# SensorController.net
KiCad netlist of a schematic drawn in EAGLE
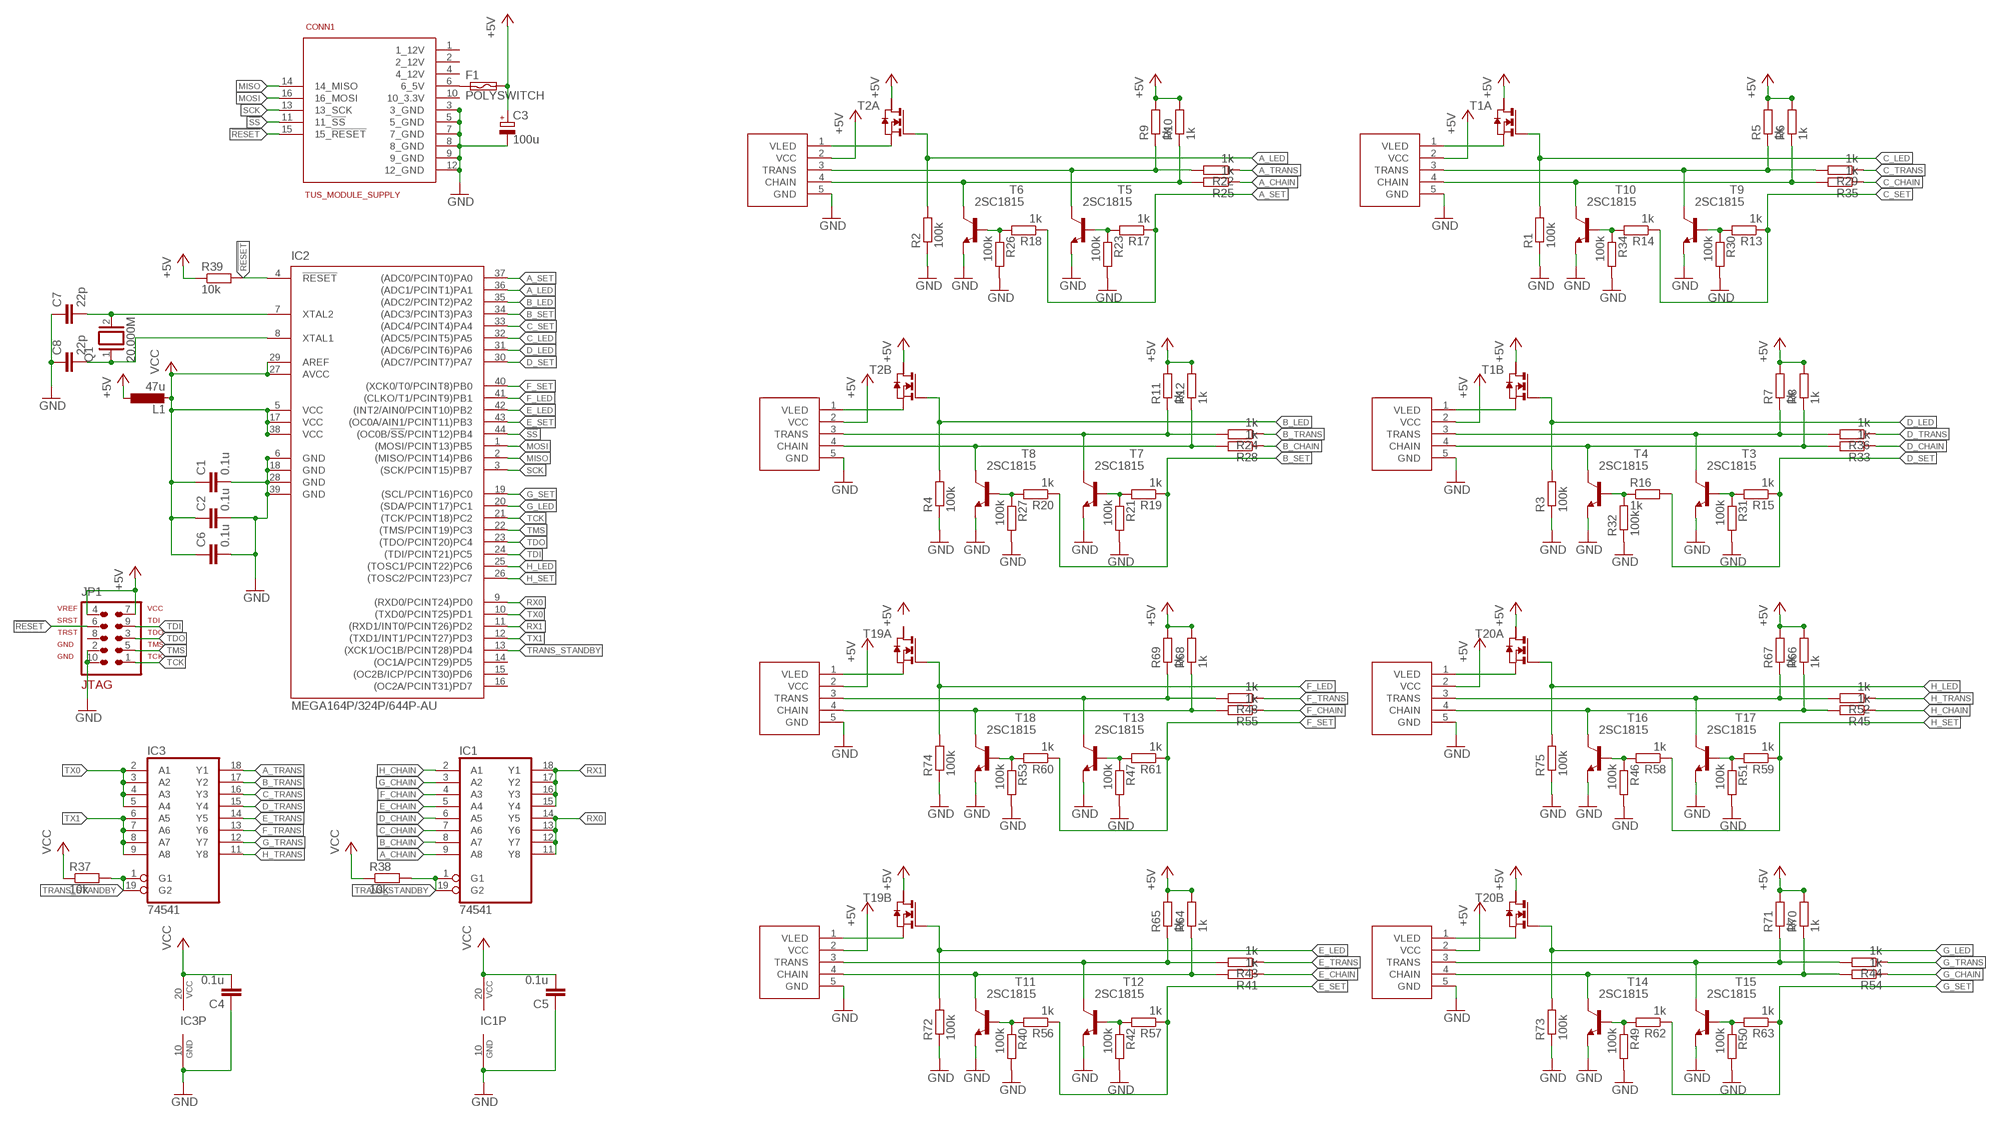
[diagram p0: schematic, sheet 1]

(export (version "E")
  (design (tool "Eeschema 10.0.6"))
  (components
    (comp (ref "A_OUT")
      (value "SERIAL_SENSORXH")
      (footprint "eagle-import:XH-5")
      (libsource (lib "eagle-import") (part "SERIAL_SENSORXH"))
    )
    (comp (ref "B_OUT")
      (value "SERIAL_SENSORXH")
      (footprint "eagle-import:XH-5")
      (libsource (lib "eagle-import") (part "SERIAL_SENSORXH"))
    )
    (comp (ref "C1")
      (value "0.1u")
      (footprint "eagle-import:C1608")
      (libsource (lib "eagle-import") (part "C-EUC1608"))
    )
    (comp (ref "C2")
      (value "0.1u")
      (footprint "eagle-import:C1608")
      (libsource (lib "eagle-import") (part "C-EUC1608"))
    )
    (comp (ref "C3")
      (value "100u")
      (footprint "eagle-import:E2,5-7")
      (libsource (lib "eagle-import") (part "CPOL-EUE2.5-7"))
    )
    (comp (ref "C4")
      (value "0.1u")
      (footprint "eagle-import:C1608")
      (libsource (lib "eagle-import") (part "C-EUC1608"))
    )
    (comp (ref "C5")
      (value "0.1u")
      (footprint "eagle-import:C1608")
      (libsource (lib "eagle-import") (part "C-EUC1608"))
    )
    (comp (ref "C6")
      (value "0.1u")
      (footprint "eagle-import:C1608")
      (libsource (lib "eagle-import") (part "C-EUC1608"))
    )
    (comp (ref "C7")
      (value "22p")
      (footprint "eagle-import:C1608")
      (libsource (lib "eagle-import") (part "C-EUC1608"))
    )
    (comp (ref "C8")
      (value "22p")
      (footprint "eagle-import:C1608")
      (libsource (lib "eagle-import") (part "C-EUC1608"))
    )
    (comp (ref "CONN1")
      (value "TUS_MODULE_SUPPLY")
      (footprint "eagle-import:2X08")
      (libsource (lib "eagle-import") (part "TUS_MODULE_SUPPLY"))
    )
    (comp (ref "C_OUT")
      (value "SERIAL_SENSORXH")
      (footprint "eagle-import:XH-5")
      (libsource (lib "eagle-import") (part "SERIAL_SENSORXH"))
    )
    (comp (ref "D_OUT")
      (value "SERIAL_SENSORXH")
      (footprint "eagle-import:XH-5")
      (libsource (lib "eagle-import") (part "SERIAL_SENSORXH"))
    )
    (comp (ref "E_OUT")
      (value "SERIAL_SENSORXH")
      (footprint "eagle-import:XH-5")
      (libsource (lib "eagle-import") (part "SERIAL_SENSORXH"))
    )
    (comp (ref "F1")
      (value "POLYSWITCH")
      (footprint "eagle-import:0207_2V")
      (libsource (lib "eagle-import") (part "POLYSWITCH"))
    )
    (comp (ref "F_OUT")
      (value "SERIAL_SENSORXH")
      (footprint "eagle-import:XH-5")
      (libsource (lib "eagle-import") (part "SERIAL_SENSORXH"))
    )
    (comp (ref "G_OUT")
      (value "SERIAL_SENSORXH")
      (footprint "eagle-import:XH-5")
      (libsource (lib "eagle-import") (part "SERIAL_SENSORXH"))
    )
    (comp (ref "H_OUT")
      (value "SERIAL_SENSORXH")
      (footprint "eagle-import:XH-5")
      (libsource (lib "eagle-import") (part "SERIAL_SENSORXH"))
    )
    (comp (ref "IC1")
      (value "74541")
      (footprint "eagle-import:SSOP20")
      (libsource (lib "eagle-import") (part "74541"))
    )
    (comp (ref "IC2")
      (value "MEGA164P/324P/644P-AU")
      (footprint "eagle-import:TQFP44")
      (libsource (lib "eagle-import") (part "MEGA164P/324P/644P-AU"))
    )
    (comp (ref "IC3")
      (value "74541")
      (footprint "eagle-import:SSOP20")
      (libsource (lib "eagle-import") (part "74541"))
    )
    (comp (ref "JP1")
      (value "AVR-JTAG-10")
      (footprint "eagle-import:AVR-JTAG-10")
      (libsource (lib "eagle-import") (part "AVR-JTAG-10"))
    )
    (comp (ref "L1")
      (value "47u")
      (footprint "eagle-import:L1812")
      (libsource (lib "eagle-import") (part "L-EUL1812"))
    )
    (comp (ref "Q1")
      (value "20.000M")
      (footprint "eagle-import:QS")
      (libsource (lib "eagle-import") (part "XTAL/S"))
    )
    (comp (ref "R1")
      (value "100k")
      (footprint "eagle-import:R0603")
      (libsource (lib "eagle-import") (part "R-EU_R0603"))
    )
    (comp (ref "R2")
      (value "100k")
      (footprint "eagle-import:R0603")
      (libsource (lib "eagle-import") (part "R-EU_R0603"))
    )
    (comp (ref "R3")
      (value "100k")
      (footprint "eagle-import:R0603")
      (libsource (lib "eagle-import") (part "R-EU_R0603"))
    )
    (comp (ref "R4")
      (value "100k")
      (footprint "eagle-import:R0603")
      (libsource (lib "eagle-import") (part "R-EU_R0603"))
    )
    (comp (ref "R5")
      (value "1k")
      (footprint "eagle-import:R0603")
      (libsource (lib "eagle-import") (part "R-EU_R0603"))
    )
    (comp (ref "R6")
      (value "1k")
      (footprint "eagle-import:R0603")
      (libsource (lib "eagle-import") (part "R-EU_R0603"))
    )
    (comp (ref "R7")
      (value "1k")
      (footprint "eagle-import:R0603")
      (libsource (lib "eagle-import") (part "R-EU_R0603"))
    )
    (comp (ref "R8")
      (value "1k")
      (footprint "eagle-import:R0603")
      (libsource (lib "eagle-import") (part "R-EU_R0603"))
    )
    (comp (ref "R9")
      (value "1k")
      (footprint "eagle-import:R0603")
      (libsource (lib "eagle-import") (part "R-EU_R0603"))
    )
    (comp (ref "R10")
      (value "1k")
      (footprint "eagle-import:R0603")
      (libsource (lib "eagle-import") (part "R-EU_R0603"))
    )
    (comp (ref "R11")
      (value "1k")
      (footprint "eagle-import:R0603")
      (libsource (lib "eagle-import") (part "R-EU_R0603"))
    )
    (comp (ref "R12")
      (value "1k")
      (footprint "eagle-import:R0603")
      (libsource (lib "eagle-import") (part "R-EU_R0603"))
    )
    (comp (ref "R13")
      (value "1k")
      (footprint "eagle-import:R0603")
      (libsource (lib "eagle-import") (part "R-EU_R0603"))
    )
    (comp (ref "R14")
      (value "1k")
      (footprint "eagle-import:R0603")
      (libsource (lib "eagle-import") (part "resistor_R-EU_R0603"))
    )
    (comp (ref "R15")
      (value "1k")
      (footprint "eagle-import:R0603")
      (libsource (lib "eagle-import") (part "R-EU_R0603"))
    )
    (comp (ref "R16")
      (value "1k")
      (footprint "eagle-import:R0603")
      (libsource (lib "eagle-import") (part "R-EU_R0603"))
    )
    (comp (ref "R17")
      (value "1k")
      (footprint "eagle-import:R0603")
      (libsource (lib "eagle-import") (part "R-EU_R0603"))
    )
    (comp (ref "R18")
      (value "1k")
      (footprint "eagle-import:R0603")
      (libsource (lib "eagle-import") (part "R-EU_R0603"))
    )
    (comp (ref "R19")
      (value "1k")
      (footprint "eagle-import:R0603")
      (libsource (lib "eagle-import") (part "R-EU_R0603"))
    )
    (comp (ref "R20")
      (value "1k")
      (footprint "eagle-import:R0603")
      (libsource (lib "eagle-import") (part "R-EU_R0603"))
    )
    (comp (ref "R21")
      (value "100k")
      (footprint "eagle-import:R0603")
      (libsource (lib "eagle-import") (part "R-EU_R0603"))
    )
    (comp (ref "R22")
      (value "1k")
      (footprint "eagle-import:R0603")
      (libsource (lib "eagle-import") (part "R-EU_R0603"))
    )
    (comp (ref "R23")
      (value "100k")
      (footprint "eagle-import:R0603")
      (libsource (lib "eagle-import") (part "R-EU_R0603"))
    )
    (comp (ref "R24")
      (value "1k")
      (footprint "eagle-import:R0603")
      (libsource (lib "eagle-import") (part "R-EU_R0603"))
    )
    (comp (ref "R25")
      (value "1k")
      (footprint "eagle-import:R0603")
      (libsource (lib "eagle-import") (part "R-EU_R0603"))
    )
    (comp (ref "R26")
      (value "100k")
      (footprint "eagle-import:R0603")
      (libsource (lib "eagle-import") (part "R-EU_R0603"))
    )
    (comp (ref "R27")
      (value "100k")
      (footprint "eagle-import:R0603")
      (libsource (lib "eagle-import") (part "R-EU_R0603"))
    )
    (comp (ref "R28")
      (value "1k")
      (footprint "eagle-import:R0603")
      (libsource (lib "eagle-import") (part "R-EU_R0603"))
    )
    (comp (ref "R29")
      (value "1k")
      (footprint "eagle-import:R0603")
      (libsource (lib "eagle-import") (part "R-EU_R0603"))
    )
    (comp (ref "R30")
      (value "100k")
      (footprint "eagle-import:R0603")
      (libsource (lib "eagle-import") (part "R-EU_R0603"))
    )
    (comp (ref "R31")
      (value "100k")
      (footprint "eagle-import:R0603")
      (libsource (lib "eagle-import") (part "R-EU_R0603"))
    )
    (comp (ref "R32")
      (value "100k")
      (footprint "eagle-import:R0603")
      (libsource (lib "eagle-import") (part "R-EU_R0603"))
    )
    (comp (ref "R33")
      (value "1k")
      (footprint "eagle-import:R0603")
      (libsource (lib "eagle-import") (part "R-EU_R0603"))
    )
    (comp (ref "R34")
      (value "100k")
      (footprint "eagle-import:R0603")
      (libsource (lib "eagle-import") (part "resistor_R-EU_R0603"))
    )
    (comp (ref "R35")
      (value "1k")
      (footprint "eagle-import:R0603")
      (libsource (lib "eagle-import") (part "R-EU_R0603"))
    )
    (comp (ref "R36")
      (value "1k")
      (footprint "eagle-import:R0603")
      (libsource (lib "eagle-import") (part "R-EU_R0603"))
    )
    (comp (ref "R37")
      (value "10k")
      (footprint "eagle-import:R0603")
      (libsource (lib "eagle-import") (part "R-EU_R0603"))
    )
    (comp (ref "R38")
      (value "10k")
      (footprint "eagle-import:R0603")
      (libsource (lib "eagle-import") (part "R-EU_R0603"))
    )
    (comp (ref "R39")
      (value "10k")
      (footprint "eagle-import:R0603")
      (libsource (lib "eagle-import") (part "R-EU_R0603"))
    )
    (comp (ref "R40")
      (value "100k")
      (footprint "eagle-import:R0603")
      (libsource (lib "eagle-import") (part "R-EU_R0603"))
    )
    (comp (ref "R41")
      (value "1k")
      (footprint "eagle-import:R0603")
      (libsource (lib "eagle-import") (part "R-EU_R0603"))
    )
    (comp (ref "R42")
      (value "100k")
      (footprint "eagle-import:R0603")
      (libsource (lib "eagle-import") (part "R-EU_R0603"))
    )
    (comp (ref "R43")
      (value "1k")
      (footprint "eagle-import:R0603")
      (libsource (lib "eagle-import") (part "R-EU_R0603"))
    )
    (comp (ref "R44")
      (value "1k")
      (footprint "eagle-import:R0603")
      (libsource (lib "eagle-import") (part "R-EU_R0603"))
    )
    (comp (ref "R45")
      (value "1k")
      (footprint "eagle-import:R0603")
      (libsource (lib "eagle-import") (part "R-EU_R0603"))
    )
    (comp (ref "R46")
      (value "100k")
      (footprint "eagle-import:R0603")
      (libsource (lib "eagle-import") (part "R-EU_R0603"))
    )
    (comp (ref "R47")
      (value "100k")
      (footprint "eagle-import:R0603")
      (libsource (lib "eagle-import") (part "R-EU_R0603"))
    )
    (comp (ref "R48")
      (value "1k")
      (footprint "eagle-import:R0603")
      (libsource (lib "eagle-import") (part "R-EU_R0603"))
    )
    (comp (ref "R49")
      (value "100k")
      (footprint "eagle-import:R0603")
      (libsource (lib "eagle-import") (part "R-EU_R0603"))
    )
    (comp (ref "R50")
      (value "100k")
      (footprint "eagle-import:R0603")
      (libsource (lib "eagle-import") (part "R-EU_R0603"))
    )
    (comp (ref "R51")
      (value "100k")
      (footprint "eagle-import:R0603")
      (libsource (lib "eagle-import") (part "R-EU_R0603"))
    )
    (comp (ref "R52")
      (value "1k")
      (footprint "eagle-import:R0603")
      (libsource (lib "eagle-import") (part "R-EU_R0603"))
    )
    (comp (ref "R53")
      (value "100k")
      (footprint "eagle-import:R0603")
      (libsource (lib "eagle-import") (part "R-EU_R0603"))
    )
    (comp (ref "R54")
      (value "1k")
      (footprint "eagle-import:R0603")
      (libsource (lib "eagle-import") (part "R-EU_R0603"))
    )
    (comp (ref "R55")
      (value "1k")
      (footprint "eagle-import:R0603")
      (libsource (lib "eagle-import") (part "R-EU_R0603"))
    )
    (comp (ref "R56")
      (value "1k")
      (footprint "eagle-import:R0603")
      (libsource (lib "eagle-import") (part "R-EU_R0603"))
    )
    (comp (ref "R57")
      (value "1k")
      (footprint "eagle-import:R0603")
      (libsource (lib "eagle-import") (part "R-EU_R0603"))
    )
    (comp (ref "R58")
      (value "1k")
      (footprint "eagle-import:R0603")
      (libsource (lib "eagle-import") (part "R-EU_R0603"))
    )
    (comp (ref "R59")
      (value "1k")
      (footprint "eagle-import:R0603")
      (libsource (lib "eagle-import") (part "R-EU_R0603"))
    )
    (comp (ref "R60")
      (value "1k")
      (footprint "eagle-import:R0603")
      (libsource (lib "eagle-import") (part "R-EU_R0603"))
    )
    (comp (ref "R61")
      (value "1k")
      (footprint "eagle-import:R0603")
      (libsource (lib "eagle-import") (part "R-EU_R0603"))
    )
    (comp (ref "R62")
      (value "1k")
      (footprint "eagle-import:R0603")
      (libsource (lib "eagle-import") (part "R-EU_R0603"))
    )
    (comp (ref "R63")
      (value "1k")
      (footprint "eagle-import:R0603")
      (libsource (lib "eagle-import") (part "R-EU_R0603"))
    )
    (comp (ref "R64")
      (value "1k")
      (footprint "eagle-import:R0603")
      (libsource (lib "eagle-import") (part "R-EU_R0603"))
    )
    (comp (ref "R65")
      (value "1k")
      (footprint "eagle-import:R0603")
      (libsource (lib "eagle-import") (part "R-EU_R0603"))
    )
    (comp (ref "R66")
      (value "1k")
      (footprint "eagle-import:R0603")
      (libsource (lib "eagle-import") (part "R-EU_R0603"))
    )
    (comp (ref "R67")
      (value "1k")
      (footprint "eagle-import:R0603")
      (libsource (lib "eagle-import") (part "R-EU_R0603"))
    )
    (comp (ref "R68")
      (value "1k")
      (footprint "eagle-import:R0603")
      (libsource (lib "eagle-import") (part "R-EU_R0603"))
    )
    (comp (ref "R69")
      (value "1k")
      (footprint "eagle-import:R0603")
      (libsource (lib "eagle-import") (part "R-EU_R0603"))
    )
    (comp (ref "R70")
      (value "1k")
      (footprint "eagle-import:R0603")
      (libsource (lib "eagle-import") (part "R-EU_R0603"))
    )
    (comp (ref "R71")
      (value "1k")
      (footprint "eagle-import:R0603")
      (libsource (lib "eagle-import") (part "R-EU_R0603"))
    )
    (comp (ref "R72")
      (value "100k")
      (footprint "eagle-import:R0603")
      (libsource (lib "eagle-import") (part "R-EU_R0603"))
    )
    (comp (ref "R73")
      (value "100k")
      (footprint "eagle-import:R0603")
      (libsource (lib "eagle-import") (part "R-EU_R0603"))
    )
    (comp (ref "R74")
      (value "100k")
      (footprint "eagle-import:R0603")
      (libsource (lib "eagle-import") (part "R-EU_R0603"))
    )
    (comp (ref "R75")
      (value "100k")
      (footprint "eagle-import:R0603")
      (libsource (lib "eagle-import") (part "R-EU_R0603"))
    )
    (comp (ref "T1")
      (value "NMOS2SO8")
      (footprint "eagle-import:SO8")
      (fields (field (name "OC_FARNELL") "unknown") (field (name "OC_NEWARK") "unknown"))
      (libsource (lib "eagle-import") (part "NMOS2SO8"))
    )
    (comp (ref "T2")
      (value "NMOS2SO8")
      (footprint "eagle-import:SO8")
      (libsource (lib "eagle-import") (part "NMOS2SO8"))
    )
    (comp (ref "T3")
      (value "2SC1815")
      (footprint "eagle-import:TO92-ECB")
      (libsource (lib "eagle-import") (part "2SC1815"))
    )
    (comp (ref "T4")
      (value "2SC1815")
      (footprint "eagle-import:TO92-ECB")
      (libsource (lib "eagle-import") (part "2SC1815"))
    )
    (comp (ref "T5")
      (value "2SC1815")
      (footprint "eagle-import:TO92-ECB")
      (libsource (lib "eagle-import") (part "2SC1815"))
    )
    (comp (ref "T6")
      (value "2SC1815")
      (footprint "eagle-import:TO92-ECB")
      (libsource (lib "eagle-import") (part "2SC1815"))
    )
    (comp (ref "T7")
      (value "2SC1815")
      (footprint "eagle-import:TO92-ECB")
      (libsource (lib "eagle-import") (part "2SC1815"))
    )
    (comp (ref "T8")
      (value "2SC1815")
      (footprint "eagle-import:TO92-ECB")
      (libsource (lib "eagle-import") (part "2SC1815"))
    )
    (comp (ref "T9")
      (value "2SC1815")
      (footprint "eagle-import:TO92-ECB")
      (libsource (lib "eagle-import") (part "2SC1815"))
    )
    (comp (ref "T10")
      (value "2SC1815")
      (footprint "eagle-import:TO92-ECB")
      (libsource (lib "eagle-import") (part "2SC1815"))
    )
    (comp (ref "T11")
      (value "2SC1815")
      (footprint "eagle-import:TO92-ECB")
      (libsource (lib "eagle-import") (part "2SC1815"))
    )
    (comp (ref "T12")
      (value "2SC1815")
      (footprint "eagle-import:TO92-ECB")
      (libsource (lib "eagle-import") (part "2SC1815"))
    )
    (comp (ref "T13")
      (value "2SC1815")
      (footprint "eagle-import:TO92-ECB")
      (libsource (lib "eagle-import") (part "2SC1815"))
    )
    (comp (ref "T14")
      (value "2SC1815")
      (footprint "eagle-import:TO92-ECB")
      (libsource (lib "eagle-import") (part "2SC1815"))
    )
    (comp (ref "T15")
      (value "2SC1815")
      (footprint "eagle-import:TO92-ECB")
      (libsource (lib "eagle-import") (part "2SC1815"))
    )
    (comp (ref "T16")
      (value "2SC1815")
      (footprint "eagle-import:TO92-ECB")
      (libsource (lib "eagle-import") (part "2SC1815"))
    )
    (comp (ref "T17")
      (value "2SC1815")
      (footprint "eagle-import:TO92-ECB")
      (libsource (lib "eagle-import") (part "2SC1815"))
    )
    (comp (ref "T18")
      (value "2SC1815")
      (footprint "eagle-import:TO92-ECB")
      (libsource (lib "eagle-import") (part "2SC1815"))
    )
    (comp (ref "T19")
      (value "NMOS2SO8")
      (footprint "eagle-import:SO8")
      (fields (field (name "OC_FARNELL") "unknown") (field (name "OC_NEWARK") "unknown"))
      (libsource (lib "eagle-import") (part "NMOS2SO8"))
    )
    (comp (ref "T20")
      (value "NMOS2SO8")
      (footprint "eagle-import:SO8")
      (fields (field (name "OC_FARNELL") "unknown") (field (name "OC_NEWARK") "unknown"))
      (libsource (lib "eagle-import") (part "NMOS2SO8"))
    )
  )
  (nets
    (net (code "1") (name "+5V") (class "Default")
      (node (ref "A_OUT") (pin "2") (pinfunction "VCC_2") (pintype "bidirectional"))
      (node (ref "B_OUT") (pin "2") (pinfunction "VCC_2") (pintype "bidirectional"))
      (node (ref "C3") (pin "+") (pinfunction "+_+") (pintype "passive"))
      (node (ref "C_OUT") (pin "2") (pinfunction "VCC_2") (pintype "bidirectional"))
      (node (ref "D_OUT") (pin "2") (pinfunction "VCC_2") (pintype "bidirectional"))
      (node (ref "E_OUT") (pin "2") (pinfunction "VCC_2") (pintype "bidirectional"))
      (node (ref "F1") (pin "2") (pinfunction "2_2") (pintype "passive"))
      (node (ref "F_OUT") (pin "2") (pinfunction "VCC_2") (pintype "bidirectional"))
      (node (ref "G_OUT") (pin "2") (pinfunction "VCC_2") (pintype "bidirectional"))
      (node (ref "H_OUT") (pin "2") (pinfunction "VCC_2") (pintype "bidirectional"))
      (node (ref "JP1") (pin "4") (pinfunction "4_4") (pintype "passive"))
      (node (ref "JP1") (pin "7") (pinfunction "7_7") (pintype "passive"))
      (node (ref "L1") (pin "1") (pinfunction "1_1") (pintype "passive"))
      (node (ref "R10") (pin "2") (pinfunction "2_2") (pintype "passive"))
      (node (ref "R11") (pin "2") (pinfunction "2_2") (pintype "passive"))
      (node (ref "R12") (pin "2") (pinfunction "2_2") (pintype "passive"))
      (node (ref "R39") (pin "1") (pinfunction "1_1") (pintype "passive"))
      (node (ref "R5") (pin "2") (pinfunction "2_2") (pintype "passive"))
      (node (ref "R6") (pin "2") (pinfunction "2_2") (pintype "passive"))
      (node (ref "R64") (pin "2") (pinfunction "2_2") (pintype "passive"))
      (node (ref "R65") (pin "2") (pinfunction "2_2") (pintype "passive"))
      (node (ref "R66") (pin "2") (pinfunction "2_2") (pintype "passive"))
      (node (ref "R67") (pin "2") (pinfunction "2_2") (pintype "passive"))
      (node (ref "R68") (pin "2") (pinfunction "2_2") (pintype "passive"))
      (node (ref "R69") (pin "2") (pinfunction "2_2") (pintype "passive"))
      (node (ref "R7") (pin "2") (pinfunction "2_2") (pintype "passive"))
      (node (ref "R70") (pin "2") (pinfunction "2_2") (pintype "passive"))
      (node (ref "R71") (pin "2") (pinfunction "2_2") (pintype "passive"))
      (node (ref "R8") (pin "2") (pinfunction "2_2") (pintype "passive"))
      (node (ref "R9") (pin "2") (pinfunction "2_2") (pintype "passive"))
      (node (ref "T1") (pin "6") (pinfunction "D_6") (pintype "passive"))
      (node (ref "T1") (pin "8") (pinfunction "D_8") (pintype "passive"))
      (node (ref "T19") (pin "6") (pinfunction "D_6") (pintype "passive"))
      (node (ref "T2") (pin "6") (pinfunction "D_6") (pintype "passive"))
      (node (ref "T2") (pin "8") (pinfunction "D_8") (pintype "passive"))
      (node (ref "T20") (pin "6") (pinfunction "D_6") (pintype "passive"))
      (node (ref "T20") (pin "8") (pinfunction "D_8") (pintype "passive"))
    )
    (net (code "2") (name "/~{RESET}") (class "Default")
      (node (ref "CONN1") (pin "15") (pinfunction "15_~{RESET}_15") (pintype "bidirectional"))
      (node (ref "IC2") (pin "4") (pinfunction "~{RESET}_4") (pintype "input"))
      (node (ref "JP1") (pin "6") (pinfunction "6_6") (pintype "passive"))
      (node (ref "R39") (pin "2") (pinfunction "2_2") (pintype "passive"))
    )
    (net (code "3") (name "/~{SS}") (class "Default")
      (node (ref "CONN1") (pin "11") (pinfunction "11_~{SS}_11") (pintype "bidirectional"))
      (node (ref "IC2") (pin "44") (pinfunction "(OC0B/~{SS}/PCINT12)PB4_44") (pintype "bidirectional"))
    )
    (net (code "4") (name "A_CHAIN") (class "Default")
      (node (ref "IC1") (pin "9") (pinfunction "A8_9") (pintype "input"))
      (node (ref "R25") (pin "1") (pinfunction "1_1") (pintype "passive"))
    )
    (net (code "5") (name "A_LED") (class "Default")
      (node (ref "IC2") (pin "36") (pinfunction "(ADC1/PCINT1)PA1_36") (pintype "bidirectional"))
      (node (ref "R2") (pin "2") (pinfunction "2_2") (pintype "passive"))
      (node (ref "T2") (pin "2") (pinfunction "G_2") (pintype "passive"))
    )
    (net (code "6") (name "A_SET") (class "Default")
      (node (ref "IC2") (pin "37") (pinfunction "(ADC0/PCINT0)PA0_37") (pintype "bidirectional"))
      (node (ref "R17") (pin "1") (pinfunction "1_1") (pintype "passive"))
      (node (ref "R18") (pin "1") (pinfunction "1_1") (pintype "passive"))
    )
    (net (code "7") (name "A_TRANS") (class "Default")
      (node (ref "IC3") (pin "18") (pinfunction "Y1_18") (pintype "tri_state"))
      (node (ref "R22") (pin "1") (pinfunction "1_1") (pintype "passive"))
    )
    (net (code "8") (name "B_CHAIN") (class "Default")
      (node (ref "IC1") (pin "8") (pinfunction "A7_8") (pintype "input"))
      (node (ref "R28") (pin "1") (pinfunction "1_1") (pintype "passive"))
    )
    (net (code "9") (name "B_LED") (class "Default")
      (node (ref "IC2") (pin "35") (pinfunction "(ADC2/PCINT2)PA2_35") (pintype "bidirectional"))
      (node (ref "R4") (pin "2") (pinfunction "2_2") (pintype "passive"))
      (node (ref "T2") (pin "4") (pinfunction "G_4") (pintype "passive"))
    )
    (net (code "10") (name "B_SET") (class "Default")
      (node (ref "IC2") (pin "34") (pinfunction "(ADC3/PCINT3)PA3_34") (pintype "bidirectional"))
      (node (ref "R19") (pin "1") (pinfunction "1_1") (pintype "passive"))
      (node (ref "R20") (pin "1") (pinfunction "1_1") (pintype "passive"))
    )
    (net (code "11") (name "B_TRANS") (class "Default")
      (node (ref "IC3") (pin "17") (pinfunction "Y2_17") (pintype "tri_state"))
      (node (ref "R24") (pin "1") (pinfunction "1_1") (pintype "passive"))
    )
    (net (code "12") (name "C_CHAIN") (class "Default")
      (node (ref "IC1") (pin "7") (pinfunction "A6_7") (pintype "input"))
      (node (ref "R35") (pin "1") (pinfunction "1_1") (pintype "passive"))
    )
    (net (code "13") (name "C_LED") (class "Default")
      (node (ref "IC2") (pin "32") (pinfunction "(ADC5/PCINT5)PA5_32") (pintype "bidirectional"))
      (node (ref "R1") (pin "2") (pinfunction "2_2") (pintype "passive"))
      (node (ref "T1") (pin "2") (pinfunction "G_2") (pintype "passive"))
    )
    (net (code "14") (name "C_SET") (class "Default")
      (node (ref "IC2") (pin "33") (pinfunction "(ADC4/PCINT4)PA4_33") (pintype "bidirectional"))
      (node (ref "R13") (pin "1") (pinfunction "1_1") (pintype "passive"))
      (node (ref "R14") (pin "1") (pinfunction "1_1") (pintype "passive"))
    )
    (net (code "15") (name "C_TRANS") (class "Default")
      (node (ref "IC3") (pin "16") (pinfunction "Y3_16") (pintype "tri_state"))
      (node (ref "R29") (pin "1") (pinfunction "1_1") (pintype "passive"))
    )
    (net (code "16") (name "D_CHAIN") (class "Default")
      (node (ref "IC1") (pin "6") (pinfunction "A5_6") (pintype "input"))
      (node (ref "R33") (pin "1") (pinfunction "1_1") (pintype "passive"))
    )
    (net (code "17") (name "D_LED") (class "Default")
      (node (ref "IC2") (pin "31") (pinfunction "(ADC6/PCINT6)PA6_31") (pintype "bidirectional"))
      (node (ref "R3") (pin "2") (pinfunction "2_2") (pintype "passive"))
      (node (ref "T1") (pin "4") (pinfunction "G_4") (pintype "passive"))
    )
    (net (code "18") (name "D_SET") (class "Default")
      (node (ref "IC2") (pin "30") (pinfunction "(ADC7/PCINT7)PA7_30") (pintype "bidirectional"))
      (node (ref "R15") (pin "1") (pinfunction "1_1") (pintype "passive"))
      (node (ref "R16") (pin "2") (pinfunction "2_2") (pintype "passive"))
    )
    (net (code "19") (name "D_TRANS") (class "Default")
      (node (ref "IC3") (pin "15") (pinfunction "Y4_15") (pintype "tri_state"))
      (node (ref "R36") (pin "1") (pinfunction "1_1") (pintype "passive"))
    )
    (net (code "20") (name "E_CHAIN") (class "Default")
      (node (ref "IC1") (pin "5") (pinfunction "A4_5") (pintype "input"))
      (node (ref "R41") (pin "1") (pinfunction "1_1") (pintype "passive"))
    )
    (net (code "21") (name "E_LED") (class "Default")
      (node (ref "IC2") (pin "42") (pinfunction "(INT2/AIN0/PCINT10)PB2_42") (pintype "bidirectional"))
      (node (ref "R72") (pin "2") (pinfunction "2_2") (pintype "passive"))
      (node (ref "T19") (pin "4") (pinfunction "G_4") (pintype "passive"))
    )
    (net (code "22") (name "E_SET") (class "Default")
      (node (ref "IC2") (pin "43") (pinfunction "(OC0A/AIN1/PCINT11)PB3_43") (pintype "bidirectional"))
      (node (ref "R56") (pin "1") (pinfunction "1_1") (pintype "passive"))
      (node (ref "R57") (pin "1") (pinfunction "1_1") (pintype "passive"))
    )
    (net (code "23") (name "E_TRANS") (class "Default")
      (node (ref "IC3") (pin "14") (pinfunction "Y5_14") (pintype "tri_state"))
      (node (ref "R43") (pin "1") (pinfunction "1_1") (pintype "passive"))
    )
    (net (code "24") (name "F_CHAIN") (class "Default")
      (node (ref "IC1") (pin "4") (pinfunction "A3_4") (pintype "input"))
      (node (ref "R55") (pin "1") (pinfunction "1_1") (pintype "passive"))
    )
    (net (code "25") (name "F_LED") (class "Default")
      (node (ref "IC2") (pin "41") (pinfunction "(CLKO/T1/PCINT9)PB1_41") (pintype "bidirectional"))
      (node (ref "R74") (pin "2") (pinfunction "2_2") (pintype "passive"))
      (node (ref "T19") (pin "2") (pinfunction "G_2") (pintype "passive"))
    )
    (net (code "26") (name "F_SET") (class "Default")
      (node (ref "IC2") (pin "40") (pinfunction "(XCK0/T0/PCINT8)PB0_40") (pintype "bidirectional"))
      (node (ref "R60") (pin "1") (pinfunction "1_1") (pintype "passive"))
      (node (ref "R61") (pin "1") (pinfunction "1_1") (pintype "passive"))
    )
    (net (code "27") (name "F_TRANS") (class "Default")
      (node (ref "IC3") (pin "13") (pinfunction "Y6_13") (pintype "tri_state"))
      (node (ref "R48") (pin "1") (pinfunction "1_1") (pintype "passive"))
    )
    (net (code "28") (name "GND") (class "Default")
      (node (ref "A_OUT") (pin "5") (pinfunction "GND_5") (pintype "bidirectional"))
      (node (ref "B_OUT") (pin "5") (pinfunction "GND_5") (pintype "bidirectional"))
      (node (ref "C1") (pin "2") (pinfunction "2_2") (pintype "passive"))
      (node (ref "C2") (pin "2") (pinfunction "2_2") (pintype "passive"))
      (node (ref "C3") (pin "-") (pinfunction "-_-") (pintype "passive"))
      (node (ref "C4") (pin "1") (pinfunction "1_1") (pintype "passive"))
      (node (ref "C5") (pin "1") (pinfunction "1_1") (pintype "passive"))
      (node (ref "C6") (pin "2") (pinfunction "2_2") (pintype "passive"))
      (node (ref "C7") (pin "1") (pinfunction "1_1") (pintype "passive"))
      (node (ref "C8") (pin "1") (pinfunction "1_1") (pintype "passive"))
      (node (ref "CONN1") (pin "12") (pinfunction "12_GND_12") (pintype "bidirectional"))
      (node (ref "CONN1") (pin "3") (pinfunction "3_GND_3") (pintype "bidirectional"))
      (node (ref "CONN1") (pin "5") (pinfunction "5_GND_5") (pintype "bidirectional"))
      (node (ref "CONN1") (pin "7") (pinfunction "7_GND_7") (pintype "bidirectional"))
      (node (ref "CONN1") (pin "8") (pinfunction "8_GND_8") (pintype "bidirectional"))
      (node (ref "CONN1") (pin "9") (pinfunction "9_GND_9") (pintype "bidirectional"))
      (node (ref "C_OUT") (pin "5") (pinfunction "GND_5") (pintype "bidirectional"))
      (node (ref "D_OUT") (pin "5") (pinfunction "GND_5") (pintype "bidirectional"))
      (node (ref "E_OUT") (pin "5") (pinfunction "GND_5") (pintype "bidirectional"))
      (node (ref "F_OUT") (pin "5") (pinfunction "GND_5") (pintype "bidirectional"))
      (node (ref "G_OUT") (pin "5") (pinfunction "GND_5") (pintype "bidirectional"))
      (node (ref "H_OUT") (pin "5") (pinfunction "GND_5") (pintype "bidirectional"))
      (node (ref "IC1") (pin "10") (pinfunction "GND_10") (pintype "power_in"))
      (node (ref "IC2") (pin "18") (pinfunction "GND_18") (pintype "power_in"))
      (node (ref "IC2") (pin "28") (pinfunction "GND_28") (pintype "power_in"))
      (node (ref "IC2") (pin "39") (pinfunction "GND_39") (pintype "power_in"))
      (node (ref "IC2") (pin "6") (pinfunction "GND_6") (pintype "power_in"))
      (node (ref "IC3") (pin "10") (pinfunction "GND_10") (pintype "power_in"))
      (node (ref "JP1") (pin "10") (pinfunction "10_10") (pintype "passive"))
      (node (ref "JP1") (pin "2") (pinfunction "2_2") (pintype "passive"))
      (node (ref "R1") (pin "1") (pinfunction "1_1") (pintype "passive"))
      (node (ref "R2") (pin "1") (pinfunction "1_1") (pintype "passive"))
      (node (ref "R21") (pin "2") (pinfunction "2_2") (pintype "passive"))
      (node (ref "R23") (pin "2") (pinfunction "2_2") (pintype "passive"))
      (node (ref "R26") (pin "2") (pinfunction "2_2") (pintype "passive"))
      (node (ref "R27") (pin "2") (pinfunction "2_2") (pintype "passive"))
      (node (ref "R3") (pin "1") (pinfunction "1_1") (pintype "passive"))
      (node (ref "R30") (pin "2") (pinfunction "2_2") (pintype "passive"))
      (node (ref "R31") (pin "2") (pinfunction "2_2") (pintype "passive"))
      (node (ref "R32") (pin "1") (pinfunction "1_1") (pintype "passive"))
      (node (ref "R34") (pin "2") (pinfunction "2_2") (pintype "passive"))
      (node (ref "R4") (pin "1") (pinfunction "1_1") (pintype "passive"))
      (node (ref "R40") (pin "2") (pinfunction "2_2") (pintype "passive"))
      (node (ref "R42") (pin "2") (pinfunction "2_2") (pintype "passive"))
      (node (ref "R46") (pin "2") (pinfunction "2_2") (pintype "passive"))
      (node (ref "R47") (pin "2") (pinfunction "2_2") (pintype "passive"))
      (node (ref "R49") (pin "2") (pinfunction "2_2") (pintype "passive"))
      (node (ref "R50") (pin "2") (pinfunction "2_2") (pintype "passive"))
      (node (ref "R51") (pin "2") (pinfunction "2_2") (pintype "passive"))
      (node (ref "R53") (pin "2") (pinfunction "2_2") (pintype "passive"))
      (node (ref "R72") (pin "1") (pinfunction "1_1") (pintype "passive"))
      (node (ref "R73") (pin "1") (pinfunction "1_1") (pintype "passive"))
      (node (ref "R74") (pin "1") (pinfunction "1_1") (pintype "passive"))
      (node (ref "R75") (pin "1") (pinfunction "1_1") (pintype "passive"))
      (node (ref "T10") (pin "E") (pinfunction "E_E") (pintype "passive"))
      (node (ref "T11") (pin "E") (pinfunction "E_E") (pintype "passive"))
      (node (ref "T12") (pin "E") (pinfunction "E_E") (pintype "passive"))
      (node (ref "T13") (pin "E") (pinfunction "E_E") (pintype "passive"))
      (node (ref "T14") (pin "E") (pinfunction "E_E") (pintype "passive"))
      (node (ref "T15") (pin "E") (pinfunction "E_E") (pintype "passive"))
      (node (ref "T16") (pin "E") (pinfunction "E_E") (pintype "passive"))
      (node (ref "T17") (pin "E") (pinfunction "E_E") (pintype "passive"))
      (node (ref "T18") (pin "E") (pinfunction "E_E") (pintype "passive"))
      (node (ref "T3") (pin "E") (pinfunction "E_E") (pintype "passive"))
      (node (ref "T4") (pin "E") (pinfunction "E_E") (pintype "passive"))
      (node (ref "T5") (pin "E") (pinfunction "E_E") (pintype "passive"))
      (node (ref "T6") (pin "E") (pinfunction "E_E") (pintype "passive"))
      (node (ref "T7") (pin "E") (pinfunction "E_E") (pintype "passive"))
      (node (ref "T8") (pin "E") (pinfunction "E_E") (pintype "passive"))
      (node (ref "T9") (pin "E") (pinfunction "E_E") (pintype "passive"))
    )
    (net (code "29") (name "G_CHAIN") (class "Default")
      (node (ref "IC1") (pin "3") (pinfunction "A2_3") (pintype "input"))
      (node (ref "R54") (pin "1") (pinfunction "1_1") (pintype "passive"))
    )
    (net (code "30") (name "G_LED") (class "Default")
      (node (ref "IC2") (pin "20") (pinfunction "(SDA/PCINT17)PC1_20") (pintype "bidirectional"))
      (node (ref "R73") (pin "2") (pinfunction "2_2") (pintype "passive"))
      (node (ref "T20") (pin "4") (pinfunction "G_4") (pintype "passive"))
    )
    (net (code "31") (name "G_SET") (class "Default")
      (node (ref "IC2") (pin "19") (pinfunction "(SCL/PCINT16)PC0_19") (pintype "bidirectional"))
      (node (ref "R62") (pin "1") (pinfunction "1_1") (pintype "passive"))
      (node (ref "R63") (pin "1") (pinfunction "1_1") (pintype "passive"))
    )
    (net (code "32") (name "G_TRANS") (class "Default")
      (node (ref "IC3") (pin "12") (pinfunction "Y7_12") (pintype "tri_state"))
      (node (ref "R44") (pin "1") (pinfunction "1_1") (pintype "passive"))
    )
    (net (code "33") (name "H_CHAIN") (class "Default")
      (node (ref "IC1") (pin "2") (pinfunction "A1_2") (pintype "input"))
      (node (ref "R45") (pin "1") (pinfunction "1_1") (pintype "passive"))
    )
    (net (code "34") (name "H_LED") (class "Default")
      (node (ref "IC2") (pin "25") (pinfunction "(TOSC1/PCINT22)PC6_25") (pintype "bidirectional"))
      (node (ref "R75") (pin "2") (pinfunction "2_2") (pintype "passive"))
      (node (ref "T20") (pin "2") (pinfunction "G_2") (pintype "passive"))
    )
    (net (code "35") (name "H_SET") (class "Default")
      (node (ref "IC2") (pin "26") (pinfunction "(TOSC2/PCINT23)PC7_26") (pintype "bidirectional"))
      (node (ref "R58") (pin "1") (pinfunction "1_1") (pintype "passive"))
      (node (ref "R59") (pin "1") (pinfunction "1_1") (pintype "passive"))
    )
    (net (code "36") (name "H_TRANS") (class "Default")
      (node (ref "IC3") (pin "11") (pinfunction "Y8_11") (pintype "tri_state"))
      (node (ref "R52") (pin "1") (pinfunction "1_1") (pintype "passive"))
    )
    (net (code "37") (name "MISO") (class "Default")
      (node (ref "CONN1") (pin "14") (pinfunction "14_MISO_14") (pintype "bidirectional"))
      (node (ref "IC2") (pin "2") (pinfunction "(MISO/PCINT14)PB6_2") (pintype "bidirectional"))
    )
    (net (code "38") (name "MOSI") (class "Default")
      (node (ref "CONN1") (pin "16") (pinfunction "16_MOSI_16") (pintype "bidirectional"))
      (node (ref "IC2") (pin "1") (pinfunction "(MOSI/PCINT13)PB5_1") (pintype "bidirectional"))
    )
    (net (code "39") (name "Net-(A_OUT-CHAIN)") (class "Default")
      (node (ref "A_OUT") (pin "4") (pinfunction "CHAIN_4") (pintype "bidirectional"))
      (node (ref "R10") (pin "1") (pinfunction "1_1") (pintype "passive"))
      (node (ref "R25") (pin "2") (pinfunction "2_2") (pintype "passive"))
      (node (ref "T6") (pin "C") (pinfunction "C_C") (pintype "passive"))
    )
    (net (code "40") (name "Net-(A_OUT-TRANS)") (class "Default")
      (node (ref "A_OUT") (pin "3") (pinfunction "TRANS_3") (pintype "bidirectional"))
      (node (ref "R22") (pin "2") (pinfunction "2_2") (pintype "passive"))
      (node (ref "R9") (pin "1") (pinfunction "1_1") (pintype "passive"))
      (node (ref "T5") (pin "C") (pinfunction "C_C") (pintype "passive"))
    )
    (net (code "41") (name "Net-(A_OUT-VLED)") (class "Default")
      (node (ref "A_OUT") (pin "1") (pinfunction "VLED_1") (pintype "bidirectional"))
      (node (ref "T2") (pin "1") (pinfunction "S_1") (pintype "passive"))
    )
    (net (code "42") (name "Net-(B_OUT-CHAIN)") (class "Default")
      (node (ref "B_OUT") (pin "4") (pinfunction "CHAIN_4") (pintype "bidirectional"))
      (node (ref "R12") (pin "1") (pinfunction "1_1") (pintype "passive"))
      (node (ref "R28") (pin "2") (pinfunction "2_2") (pintype "passive"))
      (node (ref "T8") (pin "C") (pinfunction "C_C") (pintype "passive"))
    )
    (net (code "43") (name "Net-(B_OUT-TRANS)") (class "Default")
      (node (ref "B_OUT") (pin "3") (pinfunction "TRANS_3") (pintype "bidirectional"))
      (node (ref "R11") (pin "1") (pinfunction "1_1") (pintype "passive"))
      (node (ref "R24") (pin "2") (pinfunction "2_2") (pintype "passive"))
      (node (ref "T7") (pin "C") (pinfunction "C_C") (pintype "passive"))
    )
    (net (code "44") (name "Net-(B_OUT-VLED)") (class "Default")
      (node (ref "B_OUT") (pin "1") (pinfunction "VLED_1") (pintype "bidirectional"))
      (node (ref "T2") (pin "3") (pinfunction "S_3") (pintype "passive"))
    )
    (net (code "45") (name "Net-(CONN1-6_5V)") (class "Default")
      (node (ref "CONN1") (pin "6") (pinfunction "6_5V_6") (pintype "bidirectional"))
      (node (ref "F1") (pin "1") (pinfunction "1_1") (pintype "passive"))
    )
    (net (code "46") (name "Net-(C_OUT-CHAIN)") (class "Default")
      (node (ref "C_OUT") (pin "4") (pinfunction "CHAIN_4") (pintype "bidirectional"))
      (node (ref "R35") (pin "2") (pinfunction "2_2") (pintype "passive"))
      (node (ref "R6") (pin "1") (pinfunction "1_1") (pintype "passive"))
      (node (ref "T10") (pin "C") (pinfunction "C_C") (pintype "passive"))
    )
    (net (code "47") (name "Net-(C_OUT-TRANS)") (class "Default")
      (node (ref "C_OUT") (pin "3") (pinfunction "TRANS_3") (pintype "bidirectional"))
      (node (ref "R29") (pin "2") (pinfunction "2_2") (pintype "passive"))
      (node (ref "R5") (pin "1") (pinfunction "1_1") (pintype "passive"))
      (node (ref "T9") (pin "C") (pinfunction "C_C") (pintype "passive"))
    )
    (net (code "48") (name "Net-(C_OUT-VLED)") (class "Default")
      (node (ref "C_OUT") (pin "1") (pinfunction "VLED_1") (pintype "bidirectional"))
      (node (ref "T1") (pin "1") (pinfunction "S_1") (pintype "passive"))
    )
    (net (code "49") (name "Net-(D_OUT-CHAIN)") (class "Default")
      (node (ref "D_OUT") (pin "4") (pinfunction "CHAIN_4") (pintype "bidirectional"))
      (node (ref "R33") (pin "2") (pinfunction "2_2") (pintype "passive"))
      (node (ref "R8") (pin "1") (pinfunction "1_1") (pintype "passive"))
      (node (ref "T4") (pin "C") (pinfunction "C_C") (pintype "passive"))
    )
    (net (code "50") (name "Net-(D_OUT-TRANS)") (class "Default")
      (node (ref "D_OUT") (pin "3") (pinfunction "TRANS_3") (pintype "bidirectional"))
      (node (ref "R36") (pin "2") (pinfunction "2_2") (pintype "passive"))
      (node (ref "R7") (pin "1") (pinfunction "1_1") (pintype "passive"))
      (node (ref "T3") (pin "C") (pinfunction "C_C") (pintype "passive"))
    )
    (net (code "51") (name "Net-(D_OUT-VLED)") (class "Default")
      (node (ref "D_OUT") (pin "1") (pinfunction "VLED_1") (pintype "bidirectional"))
      (node (ref "T1") (pin "3") (pinfunction "S_3") (pintype "passive"))
    )
    (net (code "52") (name "Net-(E_OUT-CHAIN)") (class "Default")
      (node (ref "E_OUT") (pin "4") (pinfunction "CHAIN_4") (pintype "bidirectional"))
      (node (ref "R41") (pin "2") (pinfunction "2_2") (pintype "passive"))
      (node (ref "R64") (pin "1") (pinfunction "1_1") (pintype "passive"))
      (node (ref "T11") (pin "C") (pinfunction "C_C") (pintype "passive"))
    )
    (net (code "53") (name "Net-(E_OUT-TRANS)") (class "Default")
      (node (ref "E_OUT") (pin "3") (pinfunction "TRANS_3") (pintype "bidirectional"))
      (node (ref "R43") (pin "2") (pinfunction "2_2") (pintype "passive"))
      (node (ref "R65") (pin "1") (pinfunction "1_1") (pintype "passive"))
      (node (ref "T12") (pin "C") (pinfunction "C_C") (pintype "passive"))
    )
    (net (code "54") (name "Net-(E_OUT-VLED)") (class "Default")
      (node (ref "E_OUT") (pin "1") (pinfunction "VLED_1") (pintype "bidirectional"))
      (node (ref "T19") (pin "3") (pinfunction "S_3") (pintype "passive"))
    )
    (net (code "55") (name "Net-(F_OUT-CHAIN)") (class "Default")
      (node (ref "F_OUT") (pin "4") (pinfunction "CHAIN_4") (pintype "bidirectional"))
      (node (ref "R55") (pin "2") (pinfunction "2_2") (pintype "passive"))
      (node (ref "R68") (pin "1") (pinfunction "1_1") (pintype "passive"))
      (node (ref "T18") (pin "C") (pinfunction "C_C") (pintype "passive"))
    )
    (net (code "56") (name "Net-(F_OUT-TRANS)") (class "Default")
      (node (ref "F_OUT") (pin "3") (pinfunction "TRANS_3") (pintype "bidirectional"))
      (node (ref "R48") (pin "2") (pinfunction "2_2") (pintype "passive"))
      (node (ref "R69") (pin "1") (pinfunction "1_1") (pintype "passive"))
      (node (ref "T13") (pin "C") (pinfunction "C_C") (pintype "passive"))
    )
    (net (code "57") (name "Net-(F_OUT-VLED)") (class "Default")
      (node (ref "F_OUT") (pin "1") (pinfunction "VLED_1") (pintype "bidirectional"))
      (node (ref "T19") (pin "1") (pinfunction "S_1") (pintype "passive"))
    )
    (net (code "58") (name "Net-(G_OUT-CHAIN)") (class "Default")
      (node (ref "G_OUT") (pin "4") (pinfunction "CHAIN_4") (pintype "bidirectional"))
      (node (ref "R54") (pin "2") (pinfunction "2_2") (pintype "passive"))
      (node (ref "R70") (pin "1") (pinfunction "1_1") (pintype "passive"))
      (node (ref "T14") (pin "C") (pinfunction "C_C") (pintype "passive"))
    )
    (net (code "59") (name "Net-(G_OUT-TRANS)") (class "Default")
      (node (ref "G_OUT") (pin "3") (pinfunction "TRANS_3") (pintype "bidirectional"))
      (node (ref "R44") (pin "2") (pinfunction "2_2") (pintype "passive"))
      (node (ref "R71") (pin "1") (pinfunction "1_1") (pintype "passive"))
      (node (ref "T15") (pin "C") (pinfunction "C_C") (pintype "passive"))
    )
    (net (code "60") (name "Net-(G_OUT-VLED)") (class "Default")
      (node (ref "G_OUT") (pin "1") (pinfunction "VLED_1") (pintype "bidirectional"))
      (node (ref "T20") (pin "3") (pinfunction "S_3") (pintype "passive"))
    )
    (net (code "61") (name "Net-(H_OUT-CHAIN)") (class "Default")
      (node (ref "H_OUT") (pin "4") (pinfunction "CHAIN_4") (pintype "bidirectional"))
      (node (ref "R45") (pin "2") (pinfunction "2_2") (pintype "passive"))
      (node (ref "R66") (pin "1") (pinfunction "1_1") (pintype "passive"))
      (node (ref "T16") (pin "C") (pinfunction "C_C") (pintype "passive"))
    )
    (net (code "62") (name "Net-(H_OUT-TRANS)") (class "Default")
      (node (ref "H_OUT") (pin "3") (pinfunction "TRANS_3") (pintype "bidirectional"))
      (node (ref "R52") (pin "2") (pinfunction "2_2") (pintype "passive"))
      (node (ref "R67") (pin "1") (pinfunction "1_1") (pintype "passive"))
      (node (ref "T17") (pin "C") (pinfunction "C_C") (pintype "passive"))
    )
    (net (code "63") (name "Net-(H_OUT-VLED)") (class "Default")
      (node (ref "H_OUT") (pin "1") (pinfunction "VLED_1") (pintype "bidirectional"))
      (node (ref "T20") (pin "1") (pinfunction "S_1") (pintype "passive"))
    )
    (net (code "64") (name "Net-(IC2-XTAL1)") (class "Default")
      (node (ref "C8") (pin "2") (pinfunction "2_2") (pintype "passive"))
      (node (ref "IC2") (pin "8") (pinfunction "XTAL1_8") (pintype "input"))
      (node (ref "Q1") (pin "1") (pinfunction "1_1") (pintype "passive"))
    )
    (net (code "65") (name "Net-(IC2-XTAL2)") (class "Default")
      (node (ref "C7") (pin "2") (pinfunction "2_2") (pintype "passive"))
      (node (ref "IC2") (pin "7") (pinfunction "XTAL2_7") (pintype "output"))
      (node (ref "Q1") (pin "2") (pinfunction "2_2") (pintype "passive"))
    )
    (net (code "66") (name "Net-(R13-Pad2)") (class "Default")
      (node (ref "R13") (pin "2") (pinfunction "2_2") (pintype "passive"))
      (node (ref "R30") (pin "1") (pinfunction "1_1") (pintype "passive"))
      (node (ref "T9") (pin "B") (pinfunction "B_B") (pintype "passive"))
    )
    (net (code "67") (name "Net-(R14-Pad2)") (class "Default")
      (node (ref "R14") (pin "2") (pinfunction "2_2") (pintype "passive"))
      (node (ref "R34") (pin "1") (pinfunction "1_1") (pintype "passive"))
      (node (ref "T10") (pin "B") (pinfunction "B_B") (pintype "passive"))
    )
    (net (code "68") (name "Net-(R15-Pad2)") (class "Default")
      (node (ref "R15") (pin "2") (pinfunction "2_2") (pintype "passive"))
      (node (ref "R31") (pin "1") (pinfunction "1_1") (pintype "passive"))
      (node (ref "T3") (pin "B") (pinfunction "B_B") (pintype "passive"))
    )
    (net (code "69") (name "Net-(R16-Pad1)") (class "Default")
      (node (ref "R16") (pin "1") (pinfunction "1_1") (pintype "passive"))
      (node (ref "R32") (pin "2") (pinfunction "2_2") (pintype "passive"))
      (node (ref "T4") (pin "B") (pinfunction "B_B") (pintype "passive"))
    )
    (net (code "70") (name "Net-(R17-Pad2)") (class "Default")
      (node (ref "R17") (pin "2") (pinfunction "2_2") (pintype "passive"))
      (node (ref "R23") (pin "1") (pinfunction "1_1") (pintype "passive"))
      (node (ref "T5") (pin "B") (pinfunction "B_B") (pintype "passive"))
    )
    (net (code "71") (name "Net-(R18-Pad2)") (class "Default")
      (node (ref "R18") (pin "2") (pinfunction "2_2") (pintype "passive"))
      (node (ref "R26") (pin "1") (pinfunction "1_1") (pintype "passive"))
      (node (ref "T6") (pin "B") (pinfunction "B_B") (pintype "passive"))
    )
    (net (code "72") (name "Net-(R19-Pad2)") (class "Default")
      (node (ref "R19") (pin "2") (pinfunction "2_2") (pintype "passive"))
      (node (ref "R21") (pin "1") (pinfunction "1_1") (pintype "passive"))
      (node (ref "T7") (pin "B") (pinfunction "B_B") (pintype "passive"))
    )
    (net (code "73") (name "Net-(R20-Pad2)") (class "Default")
      (node (ref "R20") (pin "2") (pinfunction "2_2") (pintype "passive"))
      (node (ref "R27") (pin "1") (pinfunction "1_1") (pintype "passive"))
      (node (ref "T8") (pin "B") (pinfunction "B_B") (pintype "passive"))
    )
    (net (code "74") (name "Net-(R40-Pad1)") (class "Default")
      (node (ref "R40") (pin "1") (pinfunction "1_1") (pintype "passive"))
      (node (ref "R56") (pin "2") (pinfunction "2_2") (pintype "passive"))
      (node (ref "T11") (pin "B") (pinfunction "B_B") (pintype "passive"))
    )
    (net (code "75") (name "Net-(R42-Pad1)") (class "Default")
      (node (ref "R42") (pin "1") (pinfunction "1_1") (pintype "passive"))
      (node (ref "R57") (pin "2") (pinfunction "2_2") (pintype "passive"))
      (node (ref "T12") (pin "B") (pinfunction "B_B") (pintype "passive"))
    )
    (net (code "76") (name "Net-(R46-Pad1)") (class "Default")
      (node (ref "R46") (pin "1") (pinfunction "1_1") (pintype "passive"))
      (node (ref "R58") (pin "2") (pinfunction "2_2") (pintype "passive"))
      (node (ref "T16") (pin "B") (pinfunction "B_B") (pintype "passive"))
    )
    (net (code "77") (name "Net-(R47-Pad1)") (class "Default")
      (node (ref "R47") (pin "1") (pinfunction "1_1") (pintype "passive"))
      (node (ref "R61") (pin "2") (pinfunction "2_2") (pintype "passive"))
      (node (ref "T13") (pin "B") (pinfunction "B_B") (pintype "passive"))
    )
    (net (code "78") (name "Net-(R49-Pad1)") (class "Default")
      (node (ref "R49") (pin "1") (pinfunction "1_1") (pintype "passive"))
      (node (ref "R62") (pin "2") (pinfunction "2_2") (pintype "passive"))
      (node (ref "T14") (pin "B") (pinfunction "B_B") (pintype "passive"))
    )
    (net (code "79") (name "Net-(R50-Pad1)") (class "Default")
      (node (ref "R50") (pin "1") (pinfunction "1_1") (pintype "passive"))
      (node (ref "R63") (pin "2") (pinfunction "2_2") (pintype "passive"))
      (node (ref "T15") (pin "B") (pinfunction "B_B") (pintype "passive"))
    )
    (net (code "80") (name "Net-(R51-Pad1)") (class "Default")
      (node (ref "R51") (pin "1") (pinfunction "1_1") (pintype "passive"))
      (node (ref "R59") (pin "2") (pinfunction "2_2") (pintype "passive"))
      (node (ref "T17") (pin "B") (pinfunction "B_B") (pintype "passive"))
    )
    (net (code "81") (name "Net-(R53-Pad1)") (class "Default")
      (node (ref "R53") (pin "1") (pinfunction "1_1") (pintype "passive"))
      (node (ref "R60") (pin "2") (pinfunction "2_2") (pintype "passive"))
      (node (ref "T18") (pin "B") (pinfunction "B_B") (pintype "passive"))
    )
    (net (code "82") (name "RX0") (class "Default")
      (node (ref "IC1") (pin "11") (pinfunction "Y8_11") (pintype "tri_state"))
      (node (ref "IC1") (pin "12") (pinfunction "Y7_12") (pintype "tri_state"))
      (node (ref "IC1") (pin "13") (pinfunction "Y6_13") (pintype "tri_state"))
      (node (ref "IC1") (pin "14") (pinfunction "Y5_14") (pintype "tri_state"))
      (node (ref "IC2") (pin "9") (pinfunction "(RXD0/PCINT24)PD0_9") (pintype "bidirectional"))
    )
    (net (code "83") (name "RX1") (class "Default")
      (node (ref "IC1") (pin "15") (pinfunction "Y4_15") (pintype "tri_state"))
      (node (ref "IC1") (pin "16") (pinfunction "Y3_16") (pintype "tri_state"))
      (node (ref "IC1") (pin "17") (pinfunction "Y2_17") (pintype "tri_state"))
      (node (ref "IC1") (pin "18") (pinfunction "Y1_18") (pintype "tri_state"))
      (node (ref "IC2") (pin "11") (pinfunction "(RXD1/INT0/PCINT26)PD2_11") (pintype "bidirectional"))
    )
    (net (code "84") (name "SCK") (class "Default")
      (node (ref "CONN1") (pin "13") (pinfunction "13_SCK_13") (pintype "bidirectional"))
      (node (ref "IC2") (pin "3") (pinfunction "(SCK/PCINT15)PB7_3") (pintype "bidirectional"))
    )
    (net (code "85") (name "TCK") (class "Default")
      (node (ref "IC2") (pin "21") (pinfunction "(TCK/PCINT18)PC2_21") (pintype "bidirectional"))
      (node (ref "JP1") (pin "1") (pinfunction "1_1") (pintype "passive"))
    )
    (net (code "86") (name "TDI") (class "Default")
      (node (ref "IC2") (pin "24") (pinfunction "(TDI/PCINT21)PC5_24") (pintype "bidirectional"))
      (node (ref "JP1") (pin "9") (pinfunction "9_9") (pintype "passive"))
    )
    (net (code "87") (name "TDO") (class "Default")
      (node (ref "IC2") (pin "23") (pinfunction "(TDO/PCINT20)PC4_23") (pintype "bidirectional"))
      (node (ref "JP1") (pin "3") (pinfunction "3_3") (pintype "passive"))
    )
    (net (code "88") (name "TMS") (class "Default")
      (node (ref "IC2") (pin "22") (pinfunction "(TMS/PCINT19)PC3_22") (pintype "bidirectional"))
      (node (ref "JP1") (pin "5") (pinfunction "5_5") (pintype "passive"))
    )
    (net (code "89") (name "TRANS_STANDBY") (class "Default")
      (node (ref "IC1") (pin "1") (pinfunction "G1_1") (pintype "input"))
      (node (ref "IC1") (pin "19") (pinfunction "G2_19") (pintype "input"))
      (node (ref "IC2") (pin "13") (pinfunction "(XCK1/OC1B/PCINT28)PD4_13") (pintype "bidirectional"))
      (node (ref "IC3") (pin "1") (pinfunction "G1_1") (pintype "input"))
      (node (ref "IC3") (pin "19") (pinfunction "G2_19") (pintype "input"))
      (node (ref "R37") (pin "2") (pinfunction "2_2") (pintype "passive"))
      (node (ref "R38") (pin "2") (pinfunction "2_2") (pintype "passive"))
    )
    (net (code "90") (name "TX0") (class "Default")
      (node (ref "IC2") (pin "10") (pinfunction "(TXD0/PCINT25)PD1_10") (pintype "bidirectional"))
      (node (ref "IC3") (pin "2") (pinfunction "A1_2") (pintype "input"))
      (node (ref "IC3") (pin "3") (pinfunction "A2_3") (pintype "input"))
      (node (ref "IC3") (pin "4") (pinfunction "A3_4") (pintype "input"))
      (node (ref "IC3") (pin "5") (pinfunction "A4_5") (pintype "input"))
    )
    (net (code "91") (name "TX1") (class "Default")
      (node (ref "IC2") (pin "12") (pinfunction "(TXD1/INT1/PCINT27)PD3_12") (pintype "bidirectional"))
      (node (ref "IC3") (pin "6") (pinfunction "A5_6") (pintype "input"))
      (node (ref "IC3") (pin "7") (pinfunction "A6_7") (pintype "input"))
      (node (ref "IC3") (pin "8") (pinfunction "A7_8") (pintype "input"))
      (node (ref "IC3") (pin "9") (pinfunction "A8_9") (pintype "input"))
    )
    (net (code "92") (name "VCC") (class "Default")
      (node (ref "C1") (pin "1") (pinfunction "1_1") (pintype "passive"))
      (node (ref "C2") (pin "1") (pinfunction "1_1") (pintype "passive"))
      (node (ref "C4") (pin "2") (pinfunction "2_2") (pintype "passive"))
      (node (ref "C5") (pin "2") (pinfunction "2_2") (pintype "passive"))
      (node (ref "C6") (pin "1") (pinfunction "1_1") (pintype "passive"))
      (node (ref "IC1") (pin "20") (pinfunction "VCC_20") (pintype "power_in"))
      (node (ref "IC2") (pin "17") (pinfunction "VCC_17") (pintype "power_in"))
      (node (ref "IC2") (pin "27") (pinfunction "AVCC_27") (pintype "power_in"))
      (node (ref "IC2") (pin "29") (pinfunction "AREF_29") (pintype "power_in"))
      (node (ref "IC2") (pin "38") (pinfunction "VCC_38") (pintype "power_in"))
      (node (ref "IC2") (pin "5") (pinfunction "VCC_5") (pintype "power_in"))
      (node (ref "IC3") (pin "20") (pinfunction "VCC_20") (pintype "power_in"))
      (node (ref "L1") (pin "2") (pinfunction "2_2") (pintype "passive"))
      (node (ref "R37") (pin "1") (pinfunction "1_1") (pintype "passive"))
      (node (ref "R38") (pin "1") (pinfunction "1_1") (pintype "passive"))
    )
    (net (code "93") (name "unconnected-(CONN1-1_12V-Pad1)") (class "Default")
      (node (ref "CONN1") (pin "1") (pinfunction "1_12V_1") (pintype "bidirectional"))
    )
    (net (code "94") (name "unconnected-(CONN1-2_12V-Pad2)") (class "Default")
      (node (ref "CONN1") (pin "2") (pinfunction "2_12V_2") (pintype "bidirectional"))
    )
    (net (code "95") (name "unconnected-(CONN1-4_12V-Pad4)") (class "Default")
      (node (ref "CONN1") (pin "4") (pinfunction "4_12V_4") (pintype "bidirectional"))
    )
    (net (code "96") (name "unconnected-(CONN1-10_3.3V-Pad10)") (class "Default")
      (node (ref "CONN1") (pin "10") (pinfunction "10_3.3V_10") (pintype "bidirectional"))
    )
    (net (code "97") (name "unconnected-(IC2-(OC1A{slash}PCINT29)PD5-Pad14)") (class "Default")
      (node (ref "IC2") (pin "14") (pinfunction "(OC1A/PCINT29)PD5_14") (pintype "bidirectional"))
    )
    (net (code "98") (name "unconnected-(IC2-(OC2A{slash}PCINT31)PD7-Pad16)") (class "Default")
      (node (ref "IC2") (pin "16") (pinfunction "(OC2A/PCINT31)PD7_16") (pintype "bidirectional"))
    )
    (net (code "99") (name "unconnected-(IC2-(OC2B{slash}ICP{slash}PCINT30)PD6-Pad15)") (class "Default")
      (node (ref "IC2") (pin "15") (pinfunction "(OC2B/ICP/PCINT30)PD6_15") (pintype "bidirectional"))
    )
    (net (code "100") (name "unconnected-(JP1-Pad8)") (class "Default")
      (node (ref "JP1") (pin "8") (pinfunction "8_8") (pintype "passive"))
    )
    (net (code "101") (name "unconnected-(T1A-D2-Pad7)") (class "Default")
      (node (ref "T1") (pin "7") (pinfunction "D2_7") (pintype "passive"))
    )
    (net (code "102") (name "unconnected-(T1B-D2-Pad5)") (class "Default")
      (node (ref "T1") (pin "5") (pinfunction "D2_5") (pintype "passive"))
    )
    (net (code "103") (name "unconnected-(T2A-D2-Pad7)") (class "Default")
      (node (ref "T2") (pin "7") (pinfunction "D2_7") (pintype "passive"))
    )
    (net (code "104") (name "unconnected-(T2B-D2-Pad5)") (class "Default")
      (node (ref "T2") (pin "5") (pinfunction "D2_5") (pintype "passive"))
    )
    (net (code "105") (name "unconnected-(T19A-D-Pad8)") (class "Default")
      (node (ref "T19") (pin "8") (pinfunction "D_8") (pintype "passive"))
    )
    (net (code "106") (name "unconnected-(T19A-D2-Pad7)") (class "Default")
      (node (ref "T19") (pin "7") (pinfunction "D2_7") (pintype "passive"))
    )
    (net (code "107") (name "unconnected-(T19B-D2-Pad5)") (class "Default")
      (node (ref "T19") (pin "5") (pinfunction "D2_5") (pintype "passive"))
    )
    (net (code "108") (name "unconnected-(T20A-D2-Pad7)") (class "Default")
      (node (ref "T20") (pin "7") (pinfunction "D2_7") (pintype "passive"))
    )
    (net (code "109") (name "unconnected-(T20B-D2-Pad5)") (class "Default")
      (node (ref "T20") (pin "5") (pinfunction "D2_5") (pintype "passive"))
    )
  )
)
